# chv.net
KiCad netlist of a schematic drawn in EAGLE
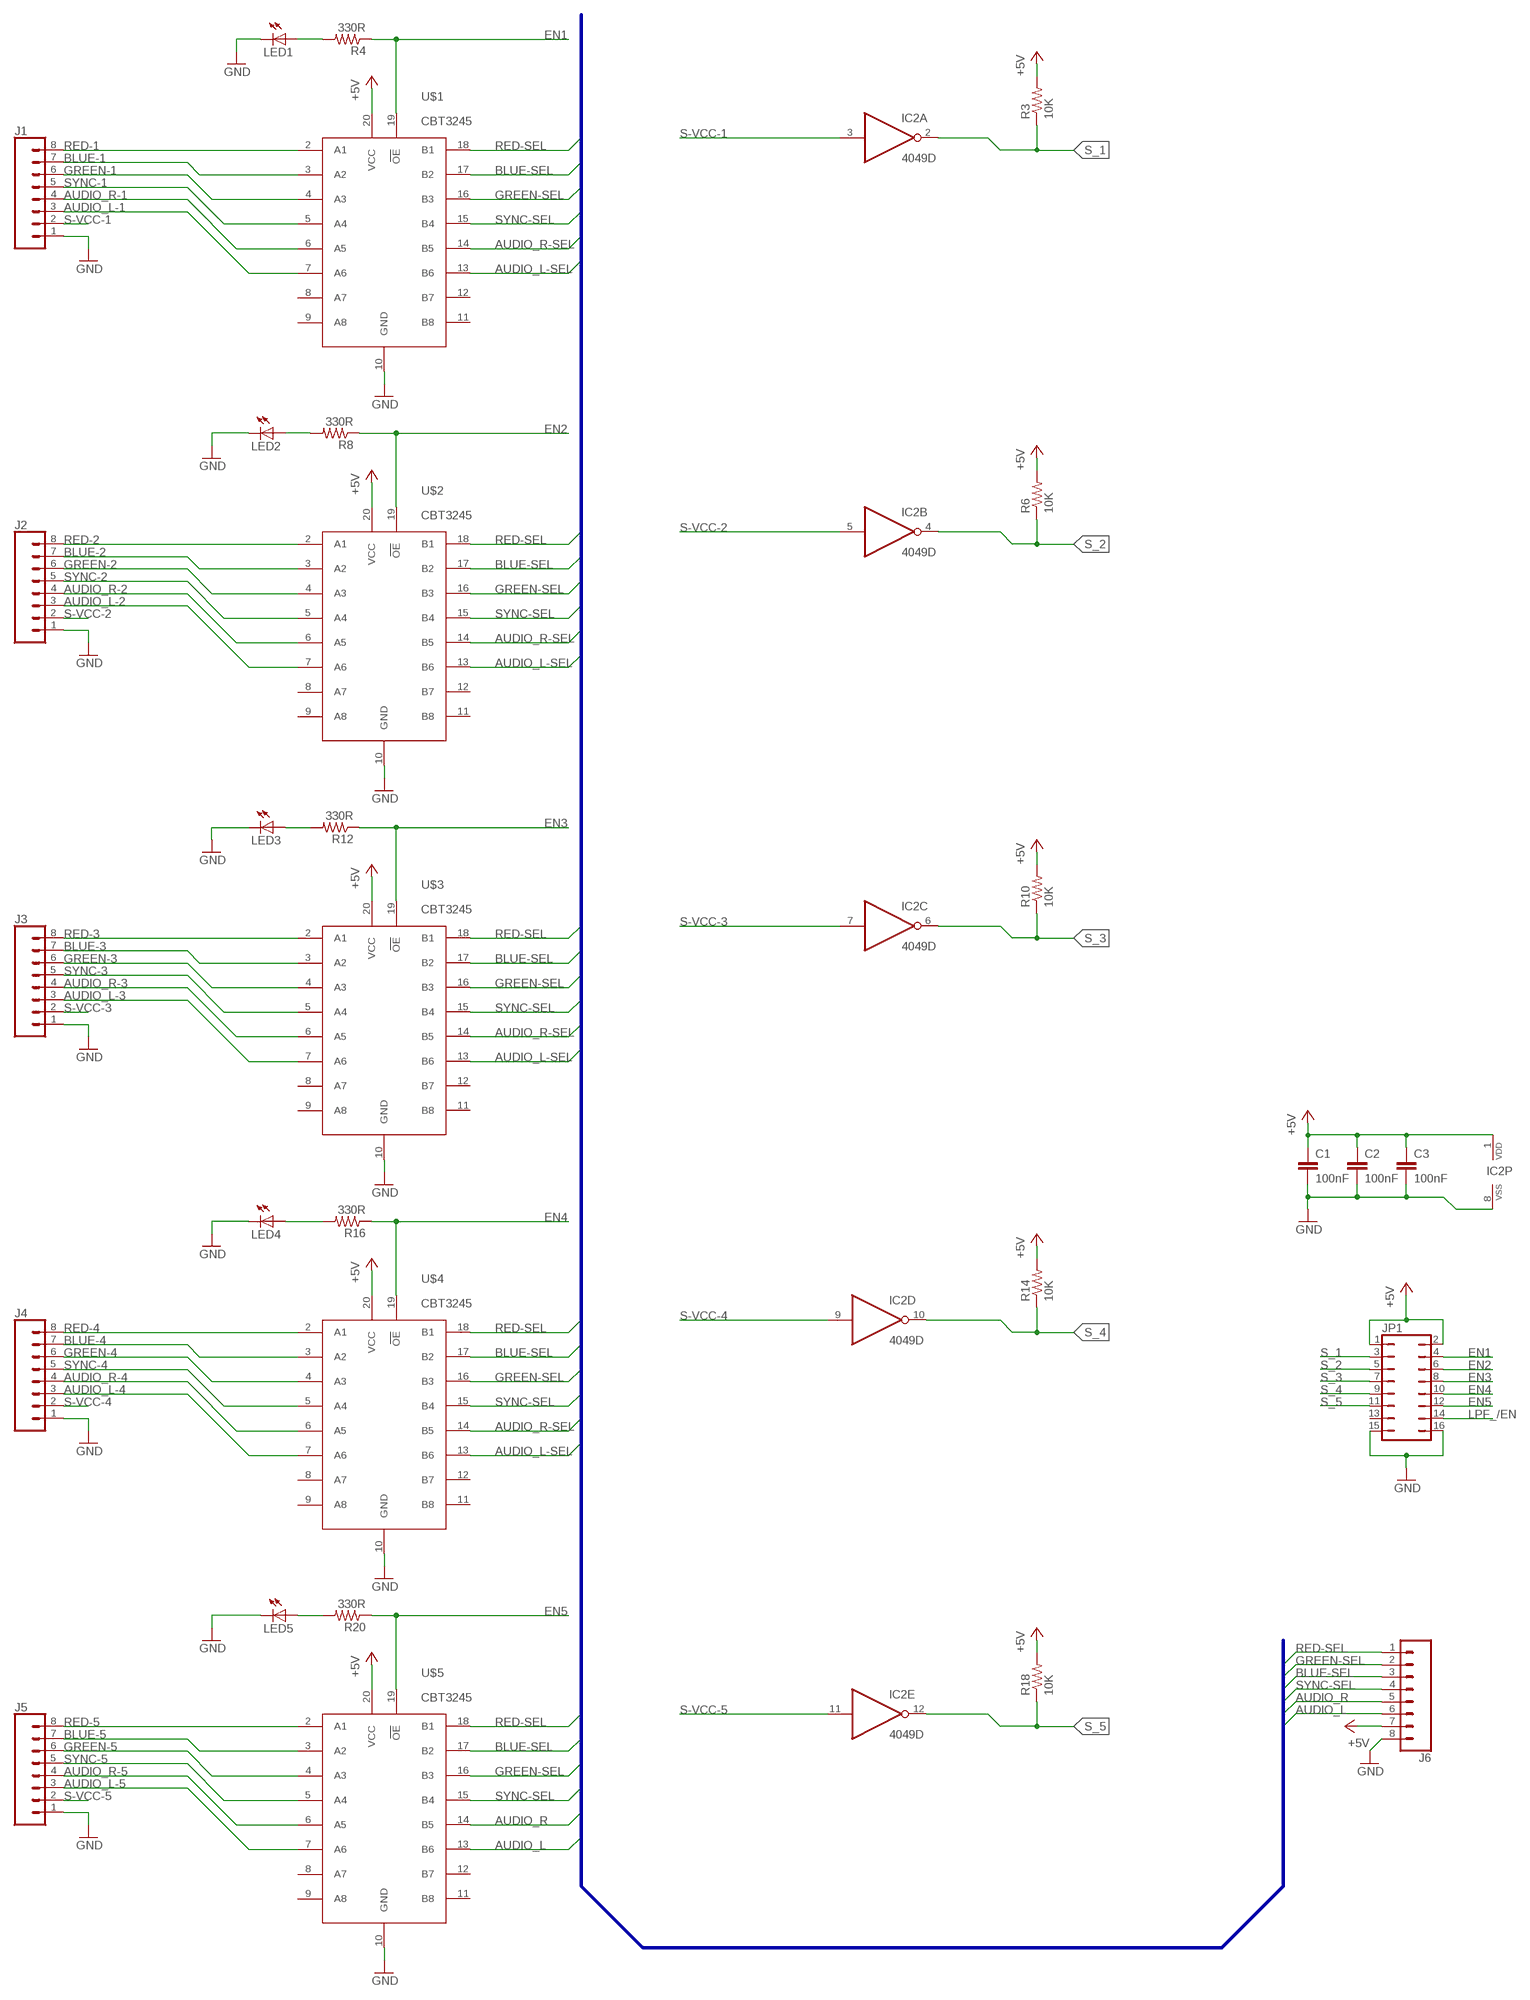
[diagram p0: schematic, sheet 1]

(export (version "E")
  (design (tool "Eeschema 10.0.6"))
  (components
    (comp (ref "C1")
      (value "100nF")
      (footprint "eagle-import:C075-032X103")
      (libsource (lib "eagle-import") (part "C-EU075-032X103"))
    )
    (comp (ref "C2")
      (value "100nF")
      (footprint "eagle-import:C075-032X103")
      (libsource (lib "eagle-import") (part "C-EU075-032X103"))
    )
    (comp (ref "C3")
      (value "100nF")
      (footprint "eagle-import:C075-032X103")
      (libsource (lib "eagle-import") (part "C-EU075-032X103"))
    )
    (comp (ref "IC2")
      (value "4049D")
      (footprint "eagle-import:SO16")
      (libsource (lib "eagle-import") (part "4049D"))
    )
    (comp (ref "J1")
      (value "CONN_08LONGPADS")
      (footprint "eagle-import:1X08_LONGPADS")
      (libsource (lib "eagle-import") (part "CONN_08LONGPADS"))
    )
    (comp (ref "J2")
      (value "CONN_08LONGPADS")
      (footprint "eagle-import:1X08_LONGPADS")
      (libsource (lib "eagle-import") (part "CONN_08LONGPADS"))
    )
    (comp (ref "J3")
      (value "CONN_08LONGPADS")
      (footprint "eagle-import:1X08_LONGPADS")
      (libsource (lib "eagle-import") (part "CONN_08LONGPADS"))
    )
    (comp (ref "J4")
      (value "CONN_08LONGPADS")
      (footprint "eagle-import:1X08_LONGPADS")
      (libsource (lib "eagle-import") (part "CONN_08LONGPADS"))
    )
    (comp (ref "J5")
      (value "CONN_08LONGPADS")
      (footprint "eagle-import:1X08_LONGPADS")
      (libsource (lib "eagle-import") (part "CONN_08LONGPADS"))
    )
    (comp (ref "J6")
      (value "CONN_08LONGPADS")
      (footprint "eagle-import:1X08_LONGPADS")
      (libsource (lib "eagle-import") (part "CONN_08LONGPADS"))
    )
    (comp (ref "JP1")
      (value "JP8Q")
      (footprint "eagle-import:JP8Q")
      (libsource (lib "eagle-import") (part "JP8Q"))
    )
    (comp (ref "LED1")
      (value "LED5MM")
      (footprint "eagle-import:LED5MM")
      (libsource (lib "eagle-import") (part "LED5MM"))
    )
    (comp (ref "LED2")
      (value "LED5MM")
      (footprint "eagle-import:LED5MM")
      (libsource (lib "eagle-import") (part "LED5MM"))
    )
    (comp (ref "LED3")
      (value "LED5MM")
      (footprint "eagle-import:LED5MM")
      (libsource (lib "eagle-import") (part "LED5MM"))
    )
    (comp (ref "LED4")
      (value "LED5MM")
      (footprint "eagle-import:LED5MM")
      (libsource (lib "eagle-import") (part "LED5MM"))
    )
    (comp (ref "LED5")
      (value "LED5MM")
      (footprint "eagle-import:LED5MM")
      (libsource (lib "eagle-import") (part "LED5MM"))
    )
    (comp (ref "R3")
      (value "10K")
      (footprint "eagle-import:0204V")
      (libsource (lib "eagle-import") (part "R-US_0204/2V"))
    )
    (comp (ref "R4")
      (value "330R")
      (footprint "eagle-import:0204V")
      (libsource (lib "eagle-import") (part "R-US_0204/2V"))
    )
    (comp (ref "R6")
      (value "10K")
      (footprint "eagle-import:0204V")
      (libsource (lib "eagle-import") (part "R-US_0204/2V"))
    )
    (comp (ref "R8")
      (value "330R")
      (footprint "eagle-import:0204V")
      (libsource (lib "eagle-import") (part "R-US_0204/2V"))
    )
    (comp (ref "R10")
      (value "10K")
      (footprint "eagle-import:0204V")
      (libsource (lib "eagle-import") (part "R-US_0204/2V"))
    )
    (comp (ref "R12")
      (value "330R")
      (footprint "eagle-import:0204V")
      (libsource (lib "eagle-import") (part "R-US_0204/2V"))
    )
    (comp (ref "R14")
      (value "10K")
      (footprint "eagle-import:0204V")
      (libsource (lib "eagle-import") (part "R-US_0204/2V"))
    )
    (comp (ref "R16")
      (value "330R")
      (footprint "eagle-import:0204V")
      (libsource (lib "eagle-import") (part "R-US_0204/2V"))
    )
    (comp (ref "R18")
      (value "10K")
      (footprint "eagle-import:0204V")
      (libsource (lib "eagle-import") (part "R-US_0204/2V"))
    )
    (comp (ref "R20")
      (value "330R")
      (footprint "eagle-import:0204V")
      (libsource (lib "eagle-import") (part "R-US_0204/2V"))
    )
    (comp (ref "U$1")
      (value "CBT3245")
      (footprint "eagle-import:SO20")
      (libsource (lib "eagle-import") (part "CBT3245"))
    )
    (comp (ref "U$2")
      (value "CBT3245")
      (footprint "eagle-import:SO20")
      (libsource (lib "eagle-import") (part "CBT3245"))
    )
    (comp (ref "U$3")
      (value "CBT3245")
      (footprint "eagle-import:SO20")
      (libsource (lib "eagle-import") (part "CBT3245"))
    )
    (comp (ref "U$4")
      (value "CBT3245")
      (footprint "eagle-import:SO20")
      (libsource (lib "eagle-import") (part "CBT3245"))
    )
    (comp (ref "U$5")
      (value "CBT3245")
      (footprint "eagle-import:SO20")
      (libsource (lib "eagle-import") (part "CBT3245"))
    )
  )
  (nets
    (net (code "1") (name "+5V") (class "Default")
      (node (ref "C1") (pin "1") (pinfunction "1_1") (pintype "passive"))
      (node (ref "C2") (pin "1") (pinfunction "1_1") (pintype "passive"))
      (node (ref "C3") (pin "1") (pinfunction "1_1") (pintype "passive"))
      (node (ref "IC2") (pin "1") (pinfunction "VDD_1") (pintype "power_in"))
      (node (ref "J6") (pin "7") (pinfunction "7_7") (pintype "passive"))
      (node (ref "JP1") (pin "1") (pinfunction "1_1") (pintype "passive"))
      (node (ref "JP1") (pin "2") (pinfunction "2_2") (pintype "passive"))
      (node (ref "R10") (pin "2") (pinfunction "2_2") (pintype "passive"))
      (node (ref "R14") (pin "2") (pinfunction "2_2") (pintype "passive"))
      (node (ref "R18") (pin "2") (pinfunction "2_2") (pintype "passive"))
      (node (ref "R3") (pin "2") (pinfunction "2_2") (pintype "passive"))
      (node (ref "R6") (pin "2") (pinfunction "2_2") (pintype "passive"))
      (node (ref "U$1") (pin "20") (pinfunction "VCC_20") (pintype "bidirectional"))
      (node (ref "U$2") (pin "20") (pinfunction "VCC_20") (pintype "bidirectional"))
      (node (ref "U$3") (pin "20") (pinfunction "VCC_20") (pintype "bidirectional"))
      (node (ref "U$4") (pin "20") (pinfunction "VCC_20") (pintype "bidirectional"))
      (node (ref "U$5") (pin "20") (pinfunction "VCC_20") (pintype "bidirectional"))
    )
    (net (code "2") (name "/AUDIO_L") (class "Default")
      (node (ref "J6") (pin "6") (pinfunction "6_6") (pintype "passive"))
      (node (ref "U$5") (pin "13") (pinfunction "B6_13") (pintype "bidirectional"))
    )
    (net (code "3") (name "/AUDIO_L-1") (class "Default")
      (node (ref "J1") (pin "3") (pinfunction "3_3") (pintype "passive"))
      (node (ref "U$1") (pin "7") (pinfunction "A6_7") (pintype "bidirectional"))
    )
    (net (code "4") (name "/AUDIO_L-2") (class "Default")
      (node (ref "J2") (pin "3") (pinfunction "3_3") (pintype "passive"))
      (node (ref "U$2") (pin "7") (pinfunction "A6_7") (pintype "bidirectional"))
    )
    (net (code "5") (name "/AUDIO_L-3") (class "Default")
      (node (ref "J3") (pin "3") (pinfunction "3_3") (pintype "passive"))
      (node (ref "U$3") (pin "7") (pinfunction "A6_7") (pintype "bidirectional"))
    )
    (net (code "6") (name "/AUDIO_L-4") (class "Default")
      (node (ref "J4") (pin "3") (pinfunction "3_3") (pintype "passive"))
      (node (ref "U$4") (pin "7") (pinfunction "A6_7") (pintype "bidirectional"))
    )
    (net (code "7") (name "/AUDIO_L-5") (class "Default")
      (node (ref "J5") (pin "3") (pinfunction "3_3") (pintype "passive"))
      (node (ref "U$5") (pin "7") (pinfunction "A6_7") (pintype "bidirectional"))
    )
    (net (code "8") (name "/AUDIO_L-SEL") (class "Default")
      (node (ref "U$1") (pin "13") (pinfunction "B6_13") (pintype "bidirectional"))
      (node (ref "U$2") (pin "13") (pinfunction "B6_13") (pintype "bidirectional"))
      (node (ref "U$3") (pin "13") (pinfunction "B6_13") (pintype "bidirectional"))
      (node (ref "U$4") (pin "13") (pinfunction "B6_13") (pintype "bidirectional"))
    )
    (net (code "9") (name "/AUDIO_R") (class "Default")
      (node (ref "J6") (pin "5") (pinfunction "5_5") (pintype "passive"))
      (node (ref "U$5") (pin "14") (pinfunction "B5_14") (pintype "bidirectional"))
    )
    (net (code "10") (name "/AUDIO_R-1") (class "Default")
      (node (ref "J1") (pin "4") (pinfunction "4_4") (pintype "passive"))
      (node (ref "U$1") (pin "6") (pinfunction "A5_6") (pintype "bidirectional"))
    )
    (net (code "11") (name "/AUDIO_R-2") (class "Default")
      (node (ref "J2") (pin "4") (pinfunction "4_4") (pintype "passive"))
      (node (ref "U$2") (pin "6") (pinfunction "A5_6") (pintype "bidirectional"))
    )
    (net (code "12") (name "/AUDIO_R-3") (class "Default")
      (node (ref "J3") (pin "4") (pinfunction "4_4") (pintype "passive"))
      (node (ref "U$3") (pin "6") (pinfunction "A5_6") (pintype "bidirectional"))
    )
    (net (code "13") (name "/AUDIO_R-4") (class "Default")
      (node (ref "J4") (pin "4") (pinfunction "4_4") (pintype "passive"))
      (node (ref "U$4") (pin "6") (pinfunction "A5_6") (pintype "bidirectional"))
    )
    (net (code "14") (name "/AUDIO_R-5") (class "Default")
      (node (ref "J5") (pin "4") (pinfunction "4_4") (pintype "passive"))
      (node (ref "U$5") (pin "6") (pinfunction "A5_6") (pintype "bidirectional"))
    )
    (net (code "15") (name "/AUDIO_R-SEL") (class "Default")
      (node (ref "U$1") (pin "14") (pinfunction "B5_14") (pintype "bidirectional"))
      (node (ref "U$2") (pin "14") (pinfunction "B5_14") (pintype "bidirectional"))
      (node (ref "U$3") (pin "14") (pinfunction "B5_14") (pintype "bidirectional"))
      (node (ref "U$4") (pin "14") (pinfunction "B5_14") (pintype "bidirectional"))
    )
    (net (code "16") (name "/BLUE-1") (class "Default")
      (node (ref "J1") (pin "7") (pinfunction "7_7") (pintype "passive"))
      (node (ref "U$1") (pin "3") (pinfunction "A2_3") (pintype "bidirectional"))
    )
    (net (code "17") (name "/BLUE-2") (class "Default")
      (node (ref "J2") (pin "7") (pinfunction "7_7") (pintype "passive"))
      (node (ref "U$2") (pin "3") (pinfunction "A2_3") (pintype "bidirectional"))
    )
    (net (code "18") (name "/BLUE-3") (class "Default")
      (node (ref "J3") (pin "7") (pinfunction "7_7") (pintype "passive"))
      (node (ref "U$3") (pin "3") (pinfunction "A2_3") (pintype "bidirectional"))
    )
    (net (code "19") (name "/BLUE-4") (class "Default")
      (node (ref "J4") (pin "7") (pinfunction "7_7") (pintype "passive"))
      (node (ref "U$4") (pin "3") (pinfunction "A2_3") (pintype "bidirectional"))
    )
    (net (code "20") (name "/BLUE-5") (class "Default")
      (node (ref "J5") (pin "7") (pinfunction "7_7") (pintype "passive"))
      (node (ref "U$5") (pin "3") (pinfunction "A2_3") (pintype "bidirectional"))
    )
    (net (code "21") (name "/BLUE-SEL") (class "Default")
      (node (ref "J6") (pin "3") (pinfunction "3_3") (pintype "passive"))
      (node (ref "U$1") (pin "17") (pinfunction "B2_17") (pintype "bidirectional"))
      (node (ref "U$2") (pin "17") (pinfunction "B2_17") (pintype "bidirectional"))
      (node (ref "U$3") (pin "17") (pinfunction "B2_17") (pintype "bidirectional"))
      (node (ref "U$4") (pin "17") (pinfunction "B2_17") (pintype "bidirectional"))
      (node (ref "U$5") (pin "17") (pinfunction "B2_17") (pintype "bidirectional"))
    )
    (net (code "22") (name "/EN1") (class "Default")
      (node (ref "JP1") (pin "4") (pinfunction "4_4") (pintype "passive"))
      (node (ref "R4") (pin "1") (pinfunction "1_1") (pintype "passive"))
      (node (ref "U$1") (pin "19") (pinfunction "OE_19") (pintype "bidirectional"))
    )
    (net (code "23") (name "/EN2") (class "Default")
      (node (ref "JP1") (pin "6") (pinfunction "6_6") (pintype "passive"))
      (node (ref "R8") (pin "1") (pinfunction "1_1") (pintype "passive"))
      (node (ref "U$2") (pin "19") (pinfunction "OE_19") (pintype "bidirectional"))
    )
    (net (code "24") (name "/EN3") (class "Default")
      (node (ref "JP1") (pin "8") (pinfunction "8_8") (pintype "passive"))
      (node (ref "R12") (pin "1") (pinfunction "1_1") (pintype "passive"))
      (node (ref "U$3") (pin "19") (pinfunction "OE_19") (pintype "bidirectional"))
    )
    (net (code "25") (name "/EN4") (class "Default")
      (node (ref "JP1") (pin "10") (pinfunction "10_10") (pintype "passive"))
      (node (ref "R16") (pin "1") (pinfunction "1_1") (pintype "passive"))
      (node (ref "U$4") (pin "19") (pinfunction "OE_19") (pintype "bidirectional"))
    )
    (net (code "26") (name "/EN5") (class "Default")
      (node (ref "JP1") (pin "12") (pinfunction "12_12") (pintype "passive"))
      (node (ref "R20") (pin "1") (pinfunction "1_1") (pintype "passive"))
      (node (ref "U$5") (pin "19") (pinfunction "OE_19") (pintype "bidirectional"))
    )
    (net (code "27") (name "/GREEN-1") (class "Default")
      (node (ref "J1") (pin "6") (pinfunction "6_6") (pintype "passive"))
      (node (ref "U$1") (pin "4") (pinfunction "A3_4") (pintype "bidirectional"))
    )
    (net (code "28") (name "/GREEN-2") (class "Default")
      (node (ref "J2") (pin "6") (pinfunction "6_6") (pintype "passive"))
      (node (ref "U$2") (pin "4") (pinfunction "A3_4") (pintype "bidirectional"))
    )
    (net (code "29") (name "/GREEN-3") (class "Default")
      (node (ref "J3") (pin "6") (pinfunction "6_6") (pintype "passive"))
      (node (ref "U$3") (pin "4") (pinfunction "A3_4") (pintype "bidirectional"))
    )
    (net (code "30") (name "/GREEN-4") (class "Default")
      (node (ref "J4") (pin "6") (pinfunction "6_6") (pintype "passive"))
      (node (ref "U$4") (pin "4") (pinfunction "A3_4") (pintype "bidirectional"))
    )
    (net (code "31") (name "/GREEN-5") (class "Default")
      (node (ref "J5") (pin "6") (pinfunction "6_6") (pintype "passive"))
      (node (ref "U$5") (pin "4") (pinfunction "A3_4") (pintype "bidirectional"))
    )
    (net (code "32") (name "/GREEN-SEL") (class "Default")
      (node (ref "J6") (pin "2") (pinfunction "2_2") (pintype "passive"))
      (node (ref "U$1") (pin "16") (pinfunction "B3_16") (pintype "bidirectional"))
      (node (ref "U$2") (pin "16") (pinfunction "B3_16") (pintype "bidirectional"))
      (node (ref "U$3") (pin "16") (pinfunction "B3_16") (pintype "bidirectional"))
      (node (ref "U$4") (pin "16") (pinfunction "B3_16") (pintype "bidirectional"))
      (node (ref "U$5") (pin "16") (pinfunction "B3_16") (pintype "bidirectional"))
    )
    (net (code "33") (name "/LPF_{slash}EN") (class "Default")
      (node (ref "JP1") (pin "14") (pinfunction "14_14") (pintype "passive"))
    )
    (net (code "34") (name "/RED-1") (class "Default")
      (node (ref "J1") (pin "8") (pinfunction "8_8") (pintype "passive"))
      (node (ref "U$1") (pin "2") (pinfunction "A1_2") (pintype "bidirectional"))
    )
    (net (code "35") (name "/RED-2") (class "Default")
      (node (ref "J2") (pin "8") (pinfunction "8_8") (pintype "passive"))
      (node (ref "U$2") (pin "2") (pinfunction "A1_2") (pintype "bidirectional"))
    )
    (net (code "36") (name "/RED-3") (class "Default")
      (node (ref "J3") (pin "8") (pinfunction "8_8") (pintype "passive"))
      (node (ref "U$3") (pin "2") (pinfunction "A1_2") (pintype "bidirectional"))
    )
    (net (code "37") (name "/RED-4") (class "Default")
      (node (ref "J4") (pin "8") (pinfunction "8_8") (pintype "passive"))
      (node (ref "U$4") (pin "2") (pinfunction "A1_2") (pintype "bidirectional"))
    )
    (net (code "38") (name "/RED-5") (class "Default")
      (node (ref "J5") (pin "8") (pinfunction "8_8") (pintype "passive"))
      (node (ref "U$5") (pin "2") (pinfunction "A1_2") (pintype "bidirectional"))
    )
    (net (code "39") (name "/RED-SEL") (class "Default")
      (node (ref "J6") (pin "1") (pinfunction "1_1") (pintype "passive"))
      (node (ref "U$1") (pin "18") (pinfunction "B1_18") (pintype "bidirectional"))
      (node (ref "U$2") (pin "18") (pinfunction "B1_18") (pintype "bidirectional"))
      (node (ref "U$3") (pin "18") (pinfunction "B1_18") (pintype "bidirectional"))
      (node (ref "U$4") (pin "18") (pinfunction "B1_18") (pintype "bidirectional"))
      (node (ref "U$5") (pin "18") (pinfunction "B1_18") (pintype "bidirectional"))
    )
    (net (code "40") (name "/S-VCC-1") (class "Default")
      (node (ref "IC2") (pin "3") (pinfunction "I_3") (pintype "input"))
      (node (ref "J1") (pin "2") (pinfunction "2_2") (pintype "passive"))
    )
    (net (code "41") (name "/S-VCC-2") (class "Default")
      (node (ref "IC2") (pin "5") (pinfunction "I_5") (pintype "input"))
      (node (ref "J2") (pin "2") (pinfunction "2_2") (pintype "passive"))
    )
    (net (code "42") (name "/S-VCC-3") (class "Default")
      (node (ref "IC2") (pin "7") (pinfunction "I_7") (pintype "input"))
      (node (ref "J3") (pin "2") (pinfunction "2_2") (pintype "passive"))
    )
    (net (code "43") (name "/S-VCC-4") (class "Default")
      (node (ref "IC2") (pin "9") (pinfunction "I_9") (pintype "input"))
      (node (ref "J4") (pin "2") (pinfunction "2_2") (pintype "passive"))
    )
    (net (code "44") (name "/S-VCC-5") (class "Default")
      (node (ref "IC2") (pin "11") (pinfunction "I_11") (pintype "input"))
      (node (ref "J5") (pin "2") (pinfunction "2_2") (pintype "passive"))
    )
    (net (code "45") (name "/SYNC-1") (class "Default")
      (node (ref "J1") (pin "5") (pinfunction "5_5") (pintype "passive"))
      (node (ref "U$1") (pin "5") (pinfunction "A4_5") (pintype "bidirectional"))
    )
    (net (code "46") (name "/SYNC-2") (class "Default")
      (node (ref "J2") (pin "5") (pinfunction "5_5") (pintype "passive"))
      (node (ref "U$2") (pin "5") (pinfunction "A4_5") (pintype "bidirectional"))
    )
    (net (code "47") (name "/SYNC-3") (class "Default")
      (node (ref "J3") (pin "5") (pinfunction "5_5") (pintype "passive"))
      (node (ref "U$3") (pin "5") (pinfunction "A4_5") (pintype "bidirectional"))
    )
    (net (code "48") (name "/SYNC-4") (class "Default")
      (node (ref "J4") (pin "5") (pinfunction "5_5") (pintype "passive"))
      (node (ref "U$4") (pin "5") (pinfunction "A4_5") (pintype "bidirectional"))
    )
    (net (code "49") (name "/SYNC-5") (class "Default")
      (node (ref "J5") (pin "5") (pinfunction "5_5") (pintype "passive"))
      (node (ref "U$5") (pin "5") (pinfunction "A4_5") (pintype "bidirectional"))
    )
    (net (code "50") (name "/SYNC-SEL") (class "Default")
      (node (ref "J6") (pin "4") (pinfunction "4_4") (pintype "passive"))
      (node (ref "U$1") (pin "15") (pinfunction "B4_15") (pintype "bidirectional"))
      (node (ref "U$2") (pin "15") (pinfunction "B4_15") (pintype "bidirectional"))
      (node (ref "U$3") (pin "15") (pinfunction "B4_15") (pintype "bidirectional"))
      (node (ref "U$4") (pin "15") (pinfunction "B4_15") (pintype "bidirectional"))
      (node (ref "U$5") (pin "15") (pinfunction "B4_15") (pintype "bidirectional"))
    )
    (net (code "51") (name "GND") (class "Default")
      (node (ref "C1") (pin "2") (pinfunction "2_2") (pintype "passive"))
      (node (ref "C2") (pin "2") (pinfunction "2_2") (pintype "passive"))
      (node (ref "C3") (pin "2") (pinfunction "2_2") (pintype "passive"))
      (node (ref "IC2") (pin "8") (pinfunction "VSS_8") (pintype "power_in"))
      (node (ref "J1") (pin "1") (pinfunction "1_1") (pintype "passive"))
      (node (ref "J2") (pin "1") (pinfunction "1_1") (pintype "passive"))
      (node (ref "J3") (pin "1") (pinfunction "1_1") (pintype "passive"))
      (node (ref "J4") (pin "1") (pinfunction "1_1") (pintype "passive"))
      (node (ref "J5") (pin "1") (pinfunction "1_1") (pintype "passive"))
      (node (ref "J6") (pin "8") (pinfunction "8_8") (pintype "passive"))
      (node (ref "JP1") (pin "15") (pinfunction "15_15") (pintype "passive"))
      (node (ref "JP1") (pin "16") (pinfunction "16_16") (pintype "passive"))
      (node (ref "LED1") (pin "K") (pinfunction "C_K") (pintype "passive"))
      (node (ref "LED2") (pin "K") (pinfunction "C_K") (pintype "passive"))
      (node (ref "LED3") (pin "K") (pinfunction "C_K") (pintype "passive"))
      (node (ref "LED4") (pin "K") (pinfunction "C_K") (pintype "passive"))
      (node (ref "LED5") (pin "K") (pinfunction "C_K") (pintype "passive"))
      (node (ref "U$1") (pin "10") (pinfunction "GND_10") (pintype "bidirectional"))
      (node (ref "U$2") (pin "10") (pinfunction "GND_10") (pintype "bidirectional"))
      (node (ref "U$3") (pin "10") (pinfunction "GND_10") (pintype "bidirectional"))
      (node (ref "U$4") (pin "10") (pinfunction "GND_10") (pintype "bidirectional"))
      (node (ref "U$5") (pin "10") (pinfunction "GND_10") (pintype "bidirectional"))
    )
    (net (code "52") (name "Net-(LED1-PadA)") (class "Default")
      (node (ref "LED1") (pin "A") (pinfunction "A_A") (pintype "passive"))
      (node (ref "R4") (pin "2") (pinfunction "2_2") (pintype "passive"))
    )
    (net (code "53") (name "Net-(LED2-PadA)") (class "Default")
      (node (ref "LED2") (pin "A") (pinfunction "A_A") (pintype "passive"))
      (node (ref "R8") (pin "2") (pinfunction "2_2") (pintype "passive"))
    )
    (net (code "54") (name "Net-(LED3-PadA)") (class "Default")
      (node (ref "LED3") (pin "A") (pinfunction "A_A") (pintype "passive"))
      (node (ref "R12") (pin "2") (pinfunction "2_2") (pintype "passive"))
    )
    (net (code "55") (name "Net-(LED4-PadA)") (class "Default")
      (node (ref "LED4") (pin "A") (pinfunction "A_A") (pintype "passive"))
      (node (ref "R16") (pin "2") (pinfunction "2_2") (pintype "passive"))
    )
    (net (code "56") (name "Net-(LED5-PadA)") (class "Default")
      (node (ref "LED5") (pin "A") (pinfunction "A_A") (pintype "passive"))
      (node (ref "R20") (pin "2") (pinfunction "2_2") (pintype "passive"))
    )
    (net (code "57") (name "S_1") (class "Default")
      (node (ref "IC2") (pin "2") (pinfunction "O_2") (pintype "output"))
      (node (ref "JP1") (pin "3") (pinfunction "3_3") (pintype "passive"))
      (node (ref "R3") (pin "1") (pinfunction "1_1") (pintype "passive"))
    )
    (net (code "58") (name "S_2") (class "Default")
      (node (ref "IC2") (pin "4") (pinfunction "O_4") (pintype "output"))
      (node (ref "JP1") (pin "5") (pinfunction "5_5") (pintype "passive"))
      (node (ref "R6") (pin "1") (pinfunction "1_1") (pintype "passive"))
    )
    (net (code "59") (name "S_3") (class "Default")
      (node (ref "IC2") (pin "6") (pinfunction "O_6") (pintype "output"))
      (node (ref "JP1") (pin "7") (pinfunction "7_7") (pintype "passive"))
      (node (ref "R10") (pin "1") (pinfunction "1_1") (pintype "passive"))
    )
    (net (code "60") (name "S_4") (class "Default")
      (node (ref "IC2") (pin "10") (pinfunction "O_10") (pintype "output"))
      (node (ref "JP1") (pin "9") (pinfunction "9_9") (pintype "passive"))
      (node (ref "R14") (pin "1") (pinfunction "1_1") (pintype "passive"))
    )
    (net (code "61") (name "S_5") (class "Default")
      (node (ref "IC2") (pin "12") (pinfunction "O_12") (pintype "output"))
      (node (ref "JP1") (pin "11") (pinfunction "11_11") (pintype "passive"))
      (node (ref "R18") (pin "1") (pinfunction "1_1") (pintype "passive"))
    )
    (net (code "62") (name "unconnected-(JP1-Pad13)") (class "Default")
      (node (ref "JP1") (pin "13") (pinfunction "13_13") (pintype "passive"))
    )
    (net (code "63") (name "unconnected-(U$1-A7-Pad8)") (class "Default")
      (node (ref "U$1") (pin "8") (pinfunction "A7_8") (pintype "bidirectional"))
    )
    (net (code "64") (name "unconnected-(U$1-A8-Pad9)") (class "Default")
      (node (ref "U$1") (pin "9") (pinfunction "A8_9") (pintype "bidirectional"))
    )
    (net (code "65") (name "unconnected-(U$1-B7-Pad12)") (class "Default")
      (node (ref "U$1") (pin "12") (pinfunction "B7_12") (pintype "bidirectional"))
    )
    (net (code "66") (name "unconnected-(U$1-B8-Pad11)") (class "Default")
      (node (ref "U$1") (pin "11") (pinfunction "B8_11") (pintype "bidirectional"))
    )
    (net (code "67") (name "unconnected-(U$2-A7-Pad8)") (class "Default")
      (node (ref "U$2") (pin "8") (pinfunction "A7_8") (pintype "bidirectional"))
    )
    (net (code "68") (name "unconnected-(U$2-A8-Pad9)") (class "Default")
      (node (ref "U$2") (pin "9") (pinfunction "A8_9") (pintype "bidirectional"))
    )
    (net (code "69") (name "unconnected-(U$2-B7-Pad12)") (class "Default")
      (node (ref "U$2") (pin "12") (pinfunction "B7_12") (pintype "bidirectional"))
    )
    (net (code "70") (name "unconnected-(U$2-B8-Pad11)") (class "Default")
      (node (ref "U$2") (pin "11") (pinfunction "B8_11") (pintype "bidirectional"))
    )
    (net (code "71") (name "unconnected-(U$3-A7-Pad8)") (class "Default")
      (node (ref "U$3") (pin "8") (pinfunction "A7_8") (pintype "bidirectional"))
    )
    (net (code "72") (name "unconnected-(U$3-A8-Pad9)") (class "Default")
      (node (ref "U$3") (pin "9") (pinfunction "A8_9") (pintype "bidirectional"))
    )
    (net (code "73") (name "unconnected-(U$3-B7-Pad12)") (class "Default")
      (node (ref "U$3") (pin "12") (pinfunction "B7_12") (pintype "bidirectional"))
    )
    (net (code "74") (name "unconnected-(U$3-B8-Pad11)") (class "Default")
      (node (ref "U$3") (pin "11") (pinfunction "B8_11") (pintype "bidirectional"))
    )
    (net (code "75") (name "unconnected-(U$4-A7-Pad8)") (class "Default")
      (node (ref "U$4") (pin "8") (pinfunction "A7_8") (pintype "bidirectional"))
    )
    (net (code "76") (name "unconnected-(U$4-A8-Pad9)") (class "Default")
      (node (ref "U$4") (pin "9") (pinfunction "A8_9") (pintype "bidirectional"))
    )
    (net (code "77") (name "unconnected-(U$4-B7-Pad12)") (class "Default")
      (node (ref "U$4") (pin "12") (pinfunction "B7_12") (pintype "bidirectional"))
    )
    (net (code "78") (name "unconnected-(U$4-B8-Pad11)") (class "Default")
      (node (ref "U$4") (pin "11") (pinfunction "B8_11") (pintype "bidirectional"))
    )
    (net (code "79") (name "unconnected-(U$5-A7-Pad8)") (class "Default")
      (node (ref "U$5") (pin "8") (pinfunction "A7_8") (pintype "bidirectional"))
    )
    (net (code "80") (name "unconnected-(U$5-A8-Pad9)") (class "Default")
      (node (ref "U$5") (pin "9") (pinfunction "A8_9") (pintype "bidirectional"))
    )
    (net (code "81") (name "unconnected-(U$5-B7-Pad12)") (class "Default")
      (node (ref "U$5") (pin "12") (pinfunction "B7_12") (pintype "bidirectional"))
    )
    (net (code "82") (name "unconnected-(U$5-B8-Pad11)") (class "Default")
      (node (ref "U$5") (pin "11") (pinfunction "B8_11") (pintype "bidirectional"))
    )
  )
)
